# Driver.net
KiCad netlist of a schematic drawn in Altium Designer
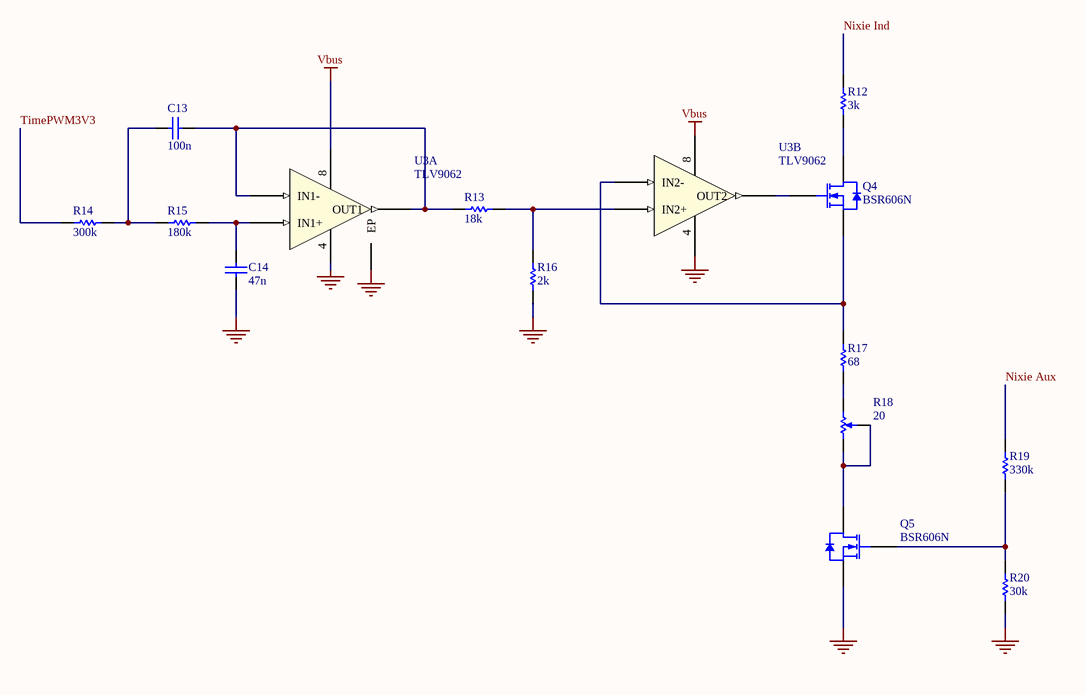
[diagram p0: Driver.SchDoc]

(export (version "E")
  (design (tool "Eeschema 10.0.6"))
  (components
    (comp (ref "C13")
      (value "100n")
      (footprint "CAPC0402(1005)60_N")
      (description "CAP CER 0.1UF 16V X7R 0402")
      (fields
        (field (name "MANUFACTURER") "Yageo")
        (field (name "MANUFACTURER PART NUMBER") "AC0402KRX7R7BB104")
      )
      (libsource (lib "0402 Caps") (part "AC0402KRX7R7BB104"))
    )
    (comp (ref "C14")
      (value "47n")
      (footprint "CAPC0402(1005)60_N")
      (description "CAP CER 0.047UF 16V X7R 0402")
      (fields
        (field (name "MANUFACTURER") "Yageo")
        (field (name "MANUFACTURER PART NUMBER") "AC0402KRX7R7BB473")
      )
      (libsource (lib "0402 Caps") (part "AC0402KRX7R7BB473"))
    )
    (comp (ref "Q4")
      (value "BSR606N")
      (footprint "INF-PG-SC59_N")
      (fields
        (field (name "MANUFACTURER") "Infineon")
        (field (name "MANUFACTURER PART NUMBER") "BSR606NH6327XTSA1")
      )
      (libsource (lib "Discretes") (part "BSR606N"))
    )
    (comp (ref "Q5")
      (value "BSR606N")
      (footprint "INF-PG-SC59_N")
      (fields
        (field (name "MANUFACTURER") "Infineon")
        (field (name "MANUFACTURER PART NUMBER") "BSR606NH6327XTSA1")
      )
      (libsource (lib "Discretes") (part "BSR606N"))
    )
    (comp (ref "R12")
      (value "3k")
      (footprint "RESC0402(1005)_N")
      (description "RES SMD 3K OHM 1% 1/16W 0402")
      (fields
        (field (name "MANUFACTURER") "Yageo")
        (field (name "MANUFACTURER PART NUMBER") "RC0402FR-073KL")
      )
      (libsource (lib "0402 Resistors") (part "RC0402FR-073KL"))
    )
    (comp (ref "R13")
      (value "18k")
      (footprint "RESC0402(1005)_N")
      (description "RES SMD 18K OHM 1% 1/16W 0402")
      (fields
        (field (name "MANUFACTURER") "Yageo")
        (field (name "MANUFACTURER PART NUMBER") "RC0402FR-0718KL")
      )
      (libsource (lib "0402 Resistors") (part "RC0402FR-0718KL"))
    )
    (comp (ref "R14")
      (value "300k")
      (footprint "RESC0402(1005)_N")
      (description "RES SMD 300K OHM 1% 1/16W 0402")
      (fields
        (field (name "MANUFACTURER") "Yageo")
        (field (name "MANUFACTURER PART NUMBER") "RC0402FR-07300KL")
      )
      (libsource (lib "0402 Resistors") (part "RC0402FR-07300KL"))
    )
    (comp (ref "R15")
      (value "180k")
      (footprint "RESC0402(1005)_N")
      (description "RES SMD 180K OHM 1% 1/16W 0402")
      (fields
        (field (name "MANUFACTURER") "Yageo")
        (field (name "MANUFACTURER PART NUMBER") "RC0402FR-07180KL")
      )
      (libsource (lib "0402 Resistors") (part "RC0402FR-07180KL"))
    )
    (comp (ref "R16")
      (value "2k")
      (footprint "RESC0402(1005)_N")
      (description "RES SMD 2K OHM 1% 1/16W 0402")
      (fields
        (field (name "MANUFACTURER") "Yageo")
        (field (name "MANUFACTURER PART NUMBER") "RC0402FR-072KL")
      )
      (libsource (lib "0402 Resistors") (part "RC0402FR-072KL"))
    )
    (comp (ref "R17")
      (value "68")
      (footprint "RESC0402(1005)_N")
      (description "RES SMD 68 OHM 1% 1/16W 0402")
      (fields
        (field (name "MANUFACTURER") "Yageo")
        (field (name "MANUFACTURER PART NUMBER") "RC0402FR-0768RL")
      )
      (libsource (lib "0402 Resistors") (part "RC0402FR-0768RL"))
    )
    (comp (ref "R18")
      (value "20")
      (footprint "PVG3A")
      (description "TRIMMER 20 OHM 0.25W J LEAD TOP")
      (fields
        (field (name "MANUFACTURER") "Bourns Inc.")
        (field (name "MANUFACTURER PART NUMBER") "PVG3A200C01R00")
      )
      (libsource (lib "Misc resistors") (part "PVG3A200C01R00"))
    )
    (comp (ref "R19")
      (value "330k")
      (footprint "RESC0402(1005)_N")
      (description "RES SMD 330K OHM 1% 1/16W 0402")
      (fields
        (field (name "MANUFACTURER") "Yageo")
        (field (name "MANUFACTURER PART NUMBER") "RC0402FR-07330KL")
      )
      (libsource (lib "0402 Resistors") (part "RC0402FR-07330KL"))
    )
    (comp (ref "R20")
      (value "30k")
      (footprint "RESC0402(1005)_N")
      (description "RES SMD 30K OHM 1% 1/16W 0402")
      (fields
        (field (name "MANUFACTURER") "Yageo")
        (field (name "MANUFACTURER PART NUMBER") "RC0402FR-0730KL")
      )
      (libsource (lib "0402 Resistors") (part "RC0402FR-0730KL"))
    )
    (comp (ref "U3")
      (value "TLV9062")
      (footprint "WSON-8")
      (description "CMOS Amplifier 2 Circuit Rail-to-Rail 8-WSON (2x2)")
      (fields
        (field (name "MANUFACTURER") "Texas Instruments")
        (field (name "MANUFACTURER PART NUMBER") "TLV9062IDSGR")
      )
      (libsource (lib "IC") (part "TLV9062IDSGR"))
    )
  )
  (nets
    (net (code "1") (name "/Nixie Aux") (class "Default")
      (node (ref "R19") (pin "2") (pinfunction "2_2") (pintype "passive"))
    )
    (net (code "2") (name "/Nixie Ind") (class "Default")
      (node (ref "R12") (pin "2") (pinfunction "2_2") (pintype "passive"))
    )
    (net (code "3") (name "/TimePWM3V3") (class "Default")
      (node (ref "R14") (pin "1") (pinfunction "1_1") (pintype "passive"))
    )
    (net (code "4") (name "GND") (class "Default")
      (node (ref "C14") (pin "1") (pinfunction "1_1") (pintype "passive"))
      (node (ref "Q5") (pin "2") (pinfunction "SOURCE_2") (pintype "passive"))
      (node (ref "R16") (pin "1") (pinfunction "1_1") (pintype "passive"))
      (node (ref "R20") (pin "1") (pinfunction "1_1") (pintype "passive"))
      (node (ref "U3") (pin "4") (pinfunction "V-_4") (pintype "power_in"))
      (node (ref "U3") (pin "9") (pinfunction "EP_9") (pintype "passive"))
    )
    (net (code "5") (name "Net-(C13-Pad1)") (class "Default")
      (node (ref "C13") (pin "1") (pinfunction "1_1") (pintype "passive"))
      (node (ref "R14") (pin "2") (pinfunction "2_2") (pintype "passive"))
      (node (ref "R15") (pin "1") (pinfunction "1_1") (pintype "passive"))
    )
    (net (code "6") (name "Net-(Q4-DRAIN)") (class "Default")
      (node (ref "Q4") (pin "3") (pinfunction "DRAIN_3") (pintype "passive"))
      (node (ref "R12") (pin "1") (pinfunction "1_1") (pintype "passive"))
    )
    (net (code "7") (name "Net-(Q4-GATE)") (class "Default")
      (node (ref "Q4") (pin "1") (pinfunction "GATE_1") (pintype "passive"))
      (node (ref "U3") (pin "7") (pinfunction "OUT2_7") (pintype "output"))
    )
    (net (code "8") (name "Net-(Q4-SOURCE)") (class "Default")
      (node (ref "Q4") (pin "2") (pinfunction "SOURCE_2") (pintype "passive"))
      (node (ref "R17") (pin "2") (pinfunction "2_2") (pintype "passive"))
      (node (ref "U3") (pin "6") (pinfunction "IN2-_6") (pintype "input"))
    )
    (net (code "9") (name "Net-(Q5-DRAIN)") (class "Default")
      (node (ref "Q5") (pin "3") (pinfunction "DRAIN_3") (pintype "passive"))
      (node (ref "R18") (pin "1") (pinfunction "1_1") (pintype "passive"))
      (node (ref "R18") (pin "2") (pinfunction "2_2") (pintype "passive"))
    )
    (net (code "10") (name "Net-(Q5-GATE)") (class "Default")
      (node (ref "Q5") (pin "1") (pinfunction "GATE_1") (pintype "passive"))
      (node (ref "R19") (pin "1") (pinfunction "1_1") (pintype "passive"))
      (node (ref "R20") (pin "2") (pinfunction "2_2") (pintype "passive"))
    )
    (net (code "11") (name "Net-(R17-Pad1)") (class "Default")
      (node (ref "R17") (pin "1") (pinfunction "1_1") (pintype "passive"))
      (node (ref "R18") (pin "3") (pinfunction "3_3") (pintype "passive"))
    )
    (net (code "12") (name "Net-(U3A-IN1+)") (class "Default")
      (node (ref "C14") (pin "2") (pinfunction "2_2") (pintype "passive"))
      (node (ref "R15") (pin "2") (pinfunction "2_2") (pintype "passive"))
      (node (ref "U3") (pin "3") (pinfunction "IN1+_3") (pintype "input"))
    )
    (net (code "13") (name "Net-(U3A-IN1-)") (class "Default")
      (node (ref "C13") (pin "2") (pinfunction "2_2") (pintype "passive"))
      (node (ref "R13") (pin "1") (pinfunction "1_1") (pintype "passive"))
      (node (ref "U3") (pin "1") (pinfunction "OUT1_1") (pintype "output"))
      (node (ref "U3") (pin "2") (pinfunction "IN1-_2") (pintype "input"))
    )
    (net (code "14") (name "Net-(U3B-IN2+)") (class "Default")
      (node (ref "R13") (pin "2") (pinfunction "2_2") (pintype "passive"))
      (node (ref "R16") (pin "2") (pinfunction "2_2") (pintype "passive"))
      (node (ref "U3") (pin "5") (pinfunction "IN2+_5") (pintype "input"))
    )
    (net (code "15") (name "Vbus") (class "Default")
      (node (ref "U3") (pin "8") (pinfunction "V+_8") (pintype "power_in"))
    )
  )
)
